# 1022.net
KiCad netlist of a schematic drawn in EAGLE
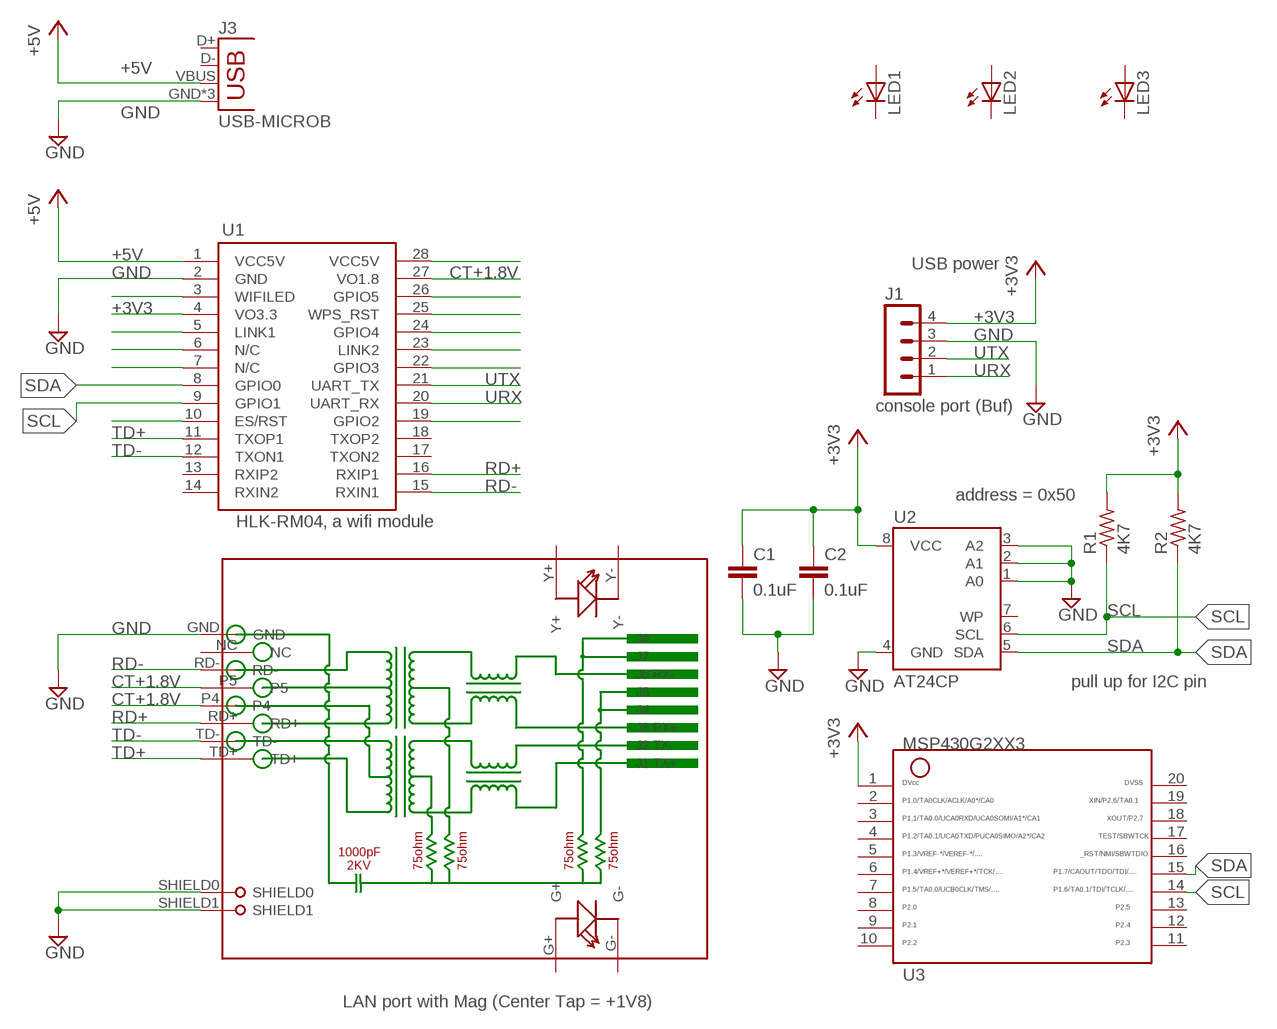
[diagram p0: schematic, sheet 1]

(export (version "E")
  (design (tool "Eeschema 10.0.6"))
  (components
    (comp (ref "C1")
      (value "0.1uF")
      (footprint "eagle-import:C0603")
      (libsource (lib "eagle-import") (part "C-EUC0603"))
    )
    (comp (ref "C2")
      (value "0.1uF")
      (footprint "eagle-import:C0603")
      (libsource (lib "eagle-import") (part "C-EUC0603"))
    )
    (comp (ref "J1")
      (value "MA04-1")
      (footprint "eagle-import:MA04-1")
      (libsource (lib "eagle-import") (part "MA04-1"))
    )
    (comp (ref "J2")
      (value "HR911105A")
      (footprint "eagle-import:HR911105A")
      (libsource (lib "eagle-import") (part "HR911105A"))
    )
    (comp (ref "J3")
      (value "USB-MICROB")
      (footprint "eagle-import:USB-MICROB")
      (libsource (lib "eagle-import") (part "USB-MICROB"))
    )
    (comp (ref "LED1")
      (value "LED3MM")
      (footprint "eagle-import:LED3MM")
      (libsource (lib "eagle-import") (part "LED3MM"))
    )
    (comp (ref "LED2")
      (value "LED3MM")
      (footprint "eagle-import:LED3MM")
      (libsource (lib "eagle-import") (part "LED3MM"))
    )
    (comp (ref "LED3")
      (value "LED3MM")
      (footprint "eagle-import:LED3MM")
      (libsource (lib "eagle-import") (part "LED3MM"))
    )
    (comp (ref "R1")
      (value "4K7")
      (footprint "eagle-import:R0603")
      (libsource (lib "eagle-import") (part "R-US_R0603"))
    )
    (comp (ref "R2")
      (value "4K7")
      (footprint "eagle-import:R0603")
      (libsource (lib "eagle-import") (part "R-US_R0603"))
    )
    (comp (ref "U1")
      (value "HLK-RM04")
      (footprint "eagle-import:HLK-RM04")
      (libsource (lib "eagle-import") (part "HLK-RM04"))
    )
    (comp (ref "U2")
      (value "AT24CP")
      (footprint "eagle-import:DIL08")
      (fields (field (name "MPN") "AT24C1024BW-SH-B"))
      (libsource (lib "eagle-import") (part "AT24CP"))
    )
    (comp (ref "U3")
      (value "G2XX3---PW20")
      (footprint "eagle-import:PW20")
      (libsource (lib "eagle-import") (part "G2XX3---PW20"))
    )
  )
  (nets
    (net (code "1") (name "+3V3") (class "Default")
      (node (ref "C1") (pin "1") (pinfunction "1_1") (pintype "passive"))
      (node (ref "C2") (pin "1") (pinfunction "1_1") (pintype "passive"))
      (node (ref "J1") (pin "4") (pinfunction "4_4") (pintype "passive"))
      (node (ref "R1") (pin "2") (pinfunction "2_2") (pintype "passive"))
      (node (ref "R2") (pin "2") (pinfunction "2_2") (pintype "passive"))
      (node (ref "U1") (pin "4") (pinfunction "VO3.3_4") (pintype "bidirectional"))
      (node (ref "U2") (pin "8") (pinfunction "VCC_8") (pintype "power_in"))
      (node (ref "U3") (pin "1") (pinfunction "1_1") (pintype "bidirectional"))
    )
    (net (code "2") (name "+5V") (class "Default")
      (node (ref "J3") (pin "VBUS") (pinfunction "VBUS_VBUS") (pintype "bidirectional"))
      (node (ref "U1") (pin "1") (pinfunction "VCC5V_1") (pintype "bidirectional"))
    )
    (net (code "3") (name "/CT+1.8V") (class "Default")
      (node (ref "J2") (pin "P4") (pinfunction "P4_P4") (pintype "bidirectional"))
      (node (ref "J2") (pin "P5") (pinfunction "P5_P5") (pintype "bidirectional"))
      (node (ref "U1") (pin "27") (pinfunction "VO1.8_27") (pintype "bidirectional"))
    )
    (net (code "4") (name "/RD+") (class "Default")
      (node (ref "J2") (pin "RD+") (pinfunction "RD+_RD+") (pintype "bidirectional"))
      (node (ref "U1") (pin "16") (pinfunction "RXIP1_16") (pintype "bidirectional"))
    )
    (net (code "5") (name "/RD-") (class "Default")
      (node (ref "J2") (pin "RD-") (pinfunction "RD-_RD-") (pintype "bidirectional"))
      (node (ref "U1") (pin "15") (pinfunction "RXIN1_15") (pintype "bidirectional"))
    )
    (net (code "6") (name "/TD+") (class "Default")
      (node (ref "J2") (pin "TD+") (pinfunction "TD+_TD+") (pintype "bidirectional"))
      (node (ref "U1") (pin "11") (pinfunction "TXOP1_11") (pintype "bidirectional"))
    )
    (net (code "7") (name "/TD-") (class "Default")
      (node (ref "J2") (pin "TD-") (pinfunction "TD-_TD-") (pintype "bidirectional"))
      (node (ref "U1") (pin "12") (pinfunction "TXON1_12") (pintype "bidirectional"))
    )
    (net (code "8") (name "/URX") (class "Default")
      (node (ref "J1") (pin "1") (pinfunction "1_1") (pintype "passive"))
      (node (ref "U1") (pin "20") (pinfunction "UART_RX_20") (pintype "bidirectional"))
    )
    (net (code "9") (name "/UTX") (class "Default")
      (node (ref "J1") (pin "2") (pinfunction "2_2") (pintype "passive"))
      (node (ref "U1") (pin "21") (pinfunction "UART_TX_21") (pintype "bidirectional"))
    )
    (net (code "10") (name "GND") (class "Default")
      (node (ref "C1") (pin "2") (pinfunction "2_2") (pintype "passive"))
      (node (ref "C2") (pin "2") (pinfunction "2_2") (pintype "passive"))
      (node (ref "J1") (pin "3") (pinfunction "3_3") (pintype "passive"))
      (node (ref "J2") (pin "GND") (pinfunction "GND_GND") (pintype "bidirectional"))
      (node (ref "J2") (pin "SHIELD0") (pinfunction "SHIELD0_SHIELD0") (pintype "bidirectional"))
      (node (ref "J2") (pin "SHIELD1") (pinfunction "SHIELD1_SHIELD1") (pintype "bidirectional"))
      (node (ref "J3") (pin "GND") (pinfunction "GND_GND") (pintype "bidirectional"))
      (node (ref "J3") (pin "MT1") (pinfunction "GND_MT1") (pintype "bidirectional"))
      (node (ref "J3") (pin "MT2") (pinfunction "GND_MT2") (pintype "bidirectional"))
      (node (ref "U1") (pin "2") (pinfunction "GND_2") (pintype "bidirectional"))
      (node (ref "U2") (pin "1") (pinfunction "A0_1") (pintype "input"))
      (node (ref "U2") (pin "2") (pinfunction "A1_2") (pintype "input"))
      (node (ref "U2") (pin "3") (pinfunction "A2_3") (pintype "input"))
      (node (ref "U2") (pin "4") (pinfunction "GND_4") (pintype "power_in"))
    )
    (net (code "11") (name "SCL") (class "Default")
      (node (ref "R1") (pin "1") (pinfunction "1_1") (pintype "passive"))
      (node (ref "U1") (pin "9") (pinfunction "GPIO1_9") (pintype "bidirectional"))
      (node (ref "U2") (pin "6") (pinfunction "SCL_6") (pintype "bidirectional"))
      (node (ref "U3") (pin "14") (pinfunction "14_14") (pintype "bidirectional"))
    )
    (net (code "12") (name "SDA") (class "Default")
      (node (ref "R2") (pin "1") (pinfunction "1_1") (pintype "passive"))
      (node (ref "U1") (pin "8") (pinfunction "GPIO0_8") (pintype "bidirectional"))
      (node (ref "U2") (pin "5") (pinfunction "SDA_5") (pintype "bidirectional"))
      (node (ref "U3") (pin "15") (pinfunction "15_15") (pintype "bidirectional"))
    )
    (net (code "13") (name "unconnected-(J2-PadG+)") (class "Default")
      (node (ref "J2") (pin "G+") (pinfunction "G+_G+") (pintype "bidirectional"))
    )
    (net (code "14") (name "unconnected-(J2-PadG-)") (class "Default")
      (node (ref "J2") (pin "G-") (pinfunction "G-_G-") (pintype "bidirectional"))
    )
    (net (code "15") (name "unconnected-(J2-PadNC)") (class "Default")
      (node (ref "J2") (pin "NC") (pinfunction "NC_NC") (pintype "bidirectional"))
    )
    (net (code "16") (name "unconnected-(J2-PadY+)") (class "Default")
      (node (ref "J2") (pin "Y+") (pinfunction "Y+_Y+") (pintype "bidirectional"))
    )
    (net (code "17") (name "unconnected-(J2-PadY-)") (class "Default")
      (node (ref "J2") (pin "Y-") (pinfunction "Y-_Y-") (pintype "bidirectional"))
    )
    (net (code "18") (name "unconnected-(J3-PadD+)") (class "Default")
      (node (ref "J3") (pin "D+") (pinfunction "D+_D+") (pintype "bidirectional"))
    )
    (net (code "19") (name "unconnected-(J3-PadD-)") (class "Default")
      (node (ref "J3") (pin "D-") (pinfunction "D-_D-") (pintype "bidirectional"))
    )
    (net (code "20") (name "unconnected-(LED1-C-PadK)") (class "Default")
      (node (ref "LED1") (pin "K") (pinfunction "C_K") (pintype "passive"))
    )
    (net (code "21") (name "unconnected-(LED1-PadA)") (class "Default")
      (node (ref "LED1") (pin "A") (pinfunction "A_A") (pintype "passive"))
    )
    (net (code "22") (name "unconnected-(LED2-C-PadK)") (class "Default")
      (node (ref "LED2") (pin "K") (pinfunction "C_K") (pintype "passive"))
    )
    (net (code "23") (name "unconnected-(LED2-PadA)") (class "Default")
      (node (ref "LED2") (pin "A") (pinfunction "A_A") (pintype "passive"))
    )
    (net (code "24") (name "unconnected-(LED3-C-PadK)") (class "Default")
      (node (ref "LED3") (pin "K") (pinfunction "C_K") (pintype "passive"))
    )
    (net (code "25") (name "unconnected-(LED3-PadA)") (class "Default")
      (node (ref "LED3") (pin "A") (pinfunction "A_A") (pintype "passive"))
    )
    (net (code "26") (name "unconnected-(U1-ES{slash}RST-Pad10)") (class "Default")
      (node (ref "U1") (pin "10") (pinfunction "ES/RST_10") (pintype "bidirectional"))
    )
    (net (code "27") (name "unconnected-(U1-GPIO2-Pad19)") (class "Default")
      (node (ref "U1") (pin "19") (pinfunction "GPIO2_19") (pintype "bidirectional"))
    )
    (net (code "28") (name "unconnected-(U1-GPIO3-Pad22)") (class "Default")
      (node (ref "U1") (pin "22") (pinfunction "GPIO3_22") (pintype "bidirectional"))
    )
    (net (code "29") (name "unconnected-(U1-GPIO4-Pad24)") (class "Default")
      (node (ref "U1") (pin "24") (pinfunction "GPIO4_24") (pintype "bidirectional"))
    )
    (net (code "30") (name "unconnected-(U1-GPIO5-Pad26)") (class "Default")
      (node (ref "U1") (pin "26") (pinfunction "GPIO5_26") (pintype "bidirectional"))
    )
    (net (code "31") (name "unconnected-(U1-LINK1-Pad5)") (class "Default")
      (node (ref "U1") (pin "5") (pinfunction "LINK1_5") (pintype "bidirectional"))
    )
    (net (code "32") (name "unconnected-(U1-LINK2-Pad23)") (class "Default")
      (node (ref "U1") (pin "23") (pinfunction "LINK2_23") (pintype "bidirectional"))
    )
    (net (code "33") (name "unconnected-(U1-N{slash}C-Pad6)") (class "Default")
      (node (ref "U1") (pin "6") (pinfunction "N/C_6") (pintype "bidirectional"))
    )
    (net (code "34") (name "unconnected-(U1-N{slash}C-Pad7)") (class "Default")
      (node (ref "U1") (pin "7") (pinfunction "N/C_7") (pintype "bidirectional"))
    )
    (net (code "35") (name "unconnected-(U1-RXIN2-Pad14)") (class "Default")
      (node (ref "U1") (pin "14") (pinfunction "RXIN2_14") (pintype "bidirectional"))
    )
    (net (code "36") (name "unconnected-(U1-RXIP2-Pad13)") (class "Default")
      (node (ref "U1") (pin "13") (pinfunction "RXIP2_13") (pintype "bidirectional"))
    )
    (net (code "37") (name "unconnected-(U1-TXON2-Pad17)") (class "Default")
      (node (ref "U1") (pin "17") (pinfunction "TXON2_17") (pintype "bidirectional"))
    )
    (net (code "38") (name "unconnected-(U1-TXOP2-Pad18)") (class "Default")
      (node (ref "U1") (pin "18") (pinfunction "TXOP2_18") (pintype "bidirectional"))
    )
    (net (code "39") (name "unconnected-(U1-VCC5V-Pad28)") (class "Default")
      (node (ref "U1") (pin "28") (pinfunction "VCC5V_28") (pintype "bidirectional"))
    )
    (net (code "40") (name "unconnected-(U1-WIFILED-Pad3)") (class "Default")
      (node (ref "U1") (pin "3") (pinfunction "WIFILED_3") (pintype "bidirectional"))
    )
    (net (code "41") (name "unconnected-(U1-WPS_RST-Pad25)") (class "Default")
      (node (ref "U1") (pin "25") (pinfunction "WPS_RST_25") (pintype "bidirectional"))
    )
    (net (code "42") (name "unconnected-(U2-WP-Pad7)") (class "Default")
      (node (ref "U2") (pin "7") (pinfunction "WP_7") (pintype "input"))
    )
    (net (code "43") (name "unconnected-(U3-Pad2)") (class "Default")
      (node (ref "U3") (pin "2") (pinfunction "2_2") (pintype "bidirectional"))
    )
    (net (code "44") (name "unconnected-(U3-Pad3)") (class "Default")
      (node (ref "U3") (pin "3") (pinfunction "3_3") (pintype "bidirectional"))
    )
    (net (code "45") (name "unconnected-(U3-Pad4)") (class "Default")
      (node (ref "U3") (pin "4") (pinfunction "4_4") (pintype "bidirectional"))
    )
    (net (code "46") (name "unconnected-(U3-Pad5)") (class "Default")
      (node (ref "U3") (pin "5") (pinfunction "5_5") (pintype "bidirectional"))
    )
    (net (code "47") (name "unconnected-(U3-Pad6)") (class "Default")
      (node (ref "U3") (pin "6") (pinfunction "6_6") (pintype "bidirectional"))
    )
    (net (code "48") (name "unconnected-(U3-Pad7)") (class "Default")
      (node (ref "U3") (pin "7") (pinfunction "7_7") (pintype "bidirectional"))
    )
    (net (code "49") (name "unconnected-(U3-Pad8)") (class "Default")
      (node (ref "U3") (pin "8") (pinfunction "8_8") (pintype "bidirectional"))
    )
    (net (code "50") (name "unconnected-(U3-Pad9)") (class "Default")
      (node (ref "U3") (pin "9") (pinfunction "9_9") (pintype "bidirectional"))
    )
    (net (code "51") (name "unconnected-(U3-Pad10)") (class "Default")
      (node (ref "U3") (pin "10") (pinfunction "10_10") (pintype "bidirectional"))
    )
    (net (code "52") (name "unconnected-(U3-Pad11)") (class "Default")
      (node (ref "U3") (pin "11") (pinfunction "11_11") (pintype "bidirectional"))
    )
    (net (code "53") (name "unconnected-(U3-Pad12)") (class "Default")
      (node (ref "U3") (pin "12") (pinfunction "12_12") (pintype "bidirectional"))
    )
    (net (code "54") (name "unconnected-(U3-Pad13)") (class "Default")
      (node (ref "U3") (pin "13") (pinfunction "13_13") (pintype "bidirectional"))
    )
    (net (code "55") (name "unconnected-(U3-Pad16)") (class "Default")
      (node (ref "U3") (pin "16") (pinfunction "16_16") (pintype "bidirectional"))
    )
    (net (code "56") (name "unconnected-(U3-Pad17)") (class "Default")
      (node (ref "U3") (pin "17") (pinfunction "17_17") (pintype "bidirectional"))
    )
    (net (code "57") (name "unconnected-(U3-Pad18)") (class "Default")
      (node (ref "U3") (pin "18") (pinfunction "18_18") (pintype "bidirectional"))
    )
    (net (code "58") (name "unconnected-(U3-Pad19)") (class "Default")
      (node (ref "U3") (pin "19") (pinfunction "19_19") (pintype "bidirectional"))
    )
    (net (code "59") (name "unconnected-(U3-Pad20)") (class "Default")
      (node (ref "U3") (pin "20") (pinfunction "20_20") (pintype "bidirectional"))
    )
  )
)
